# PlacaComNode.net
KiCad netlist of a schematic drawn in EAGLE
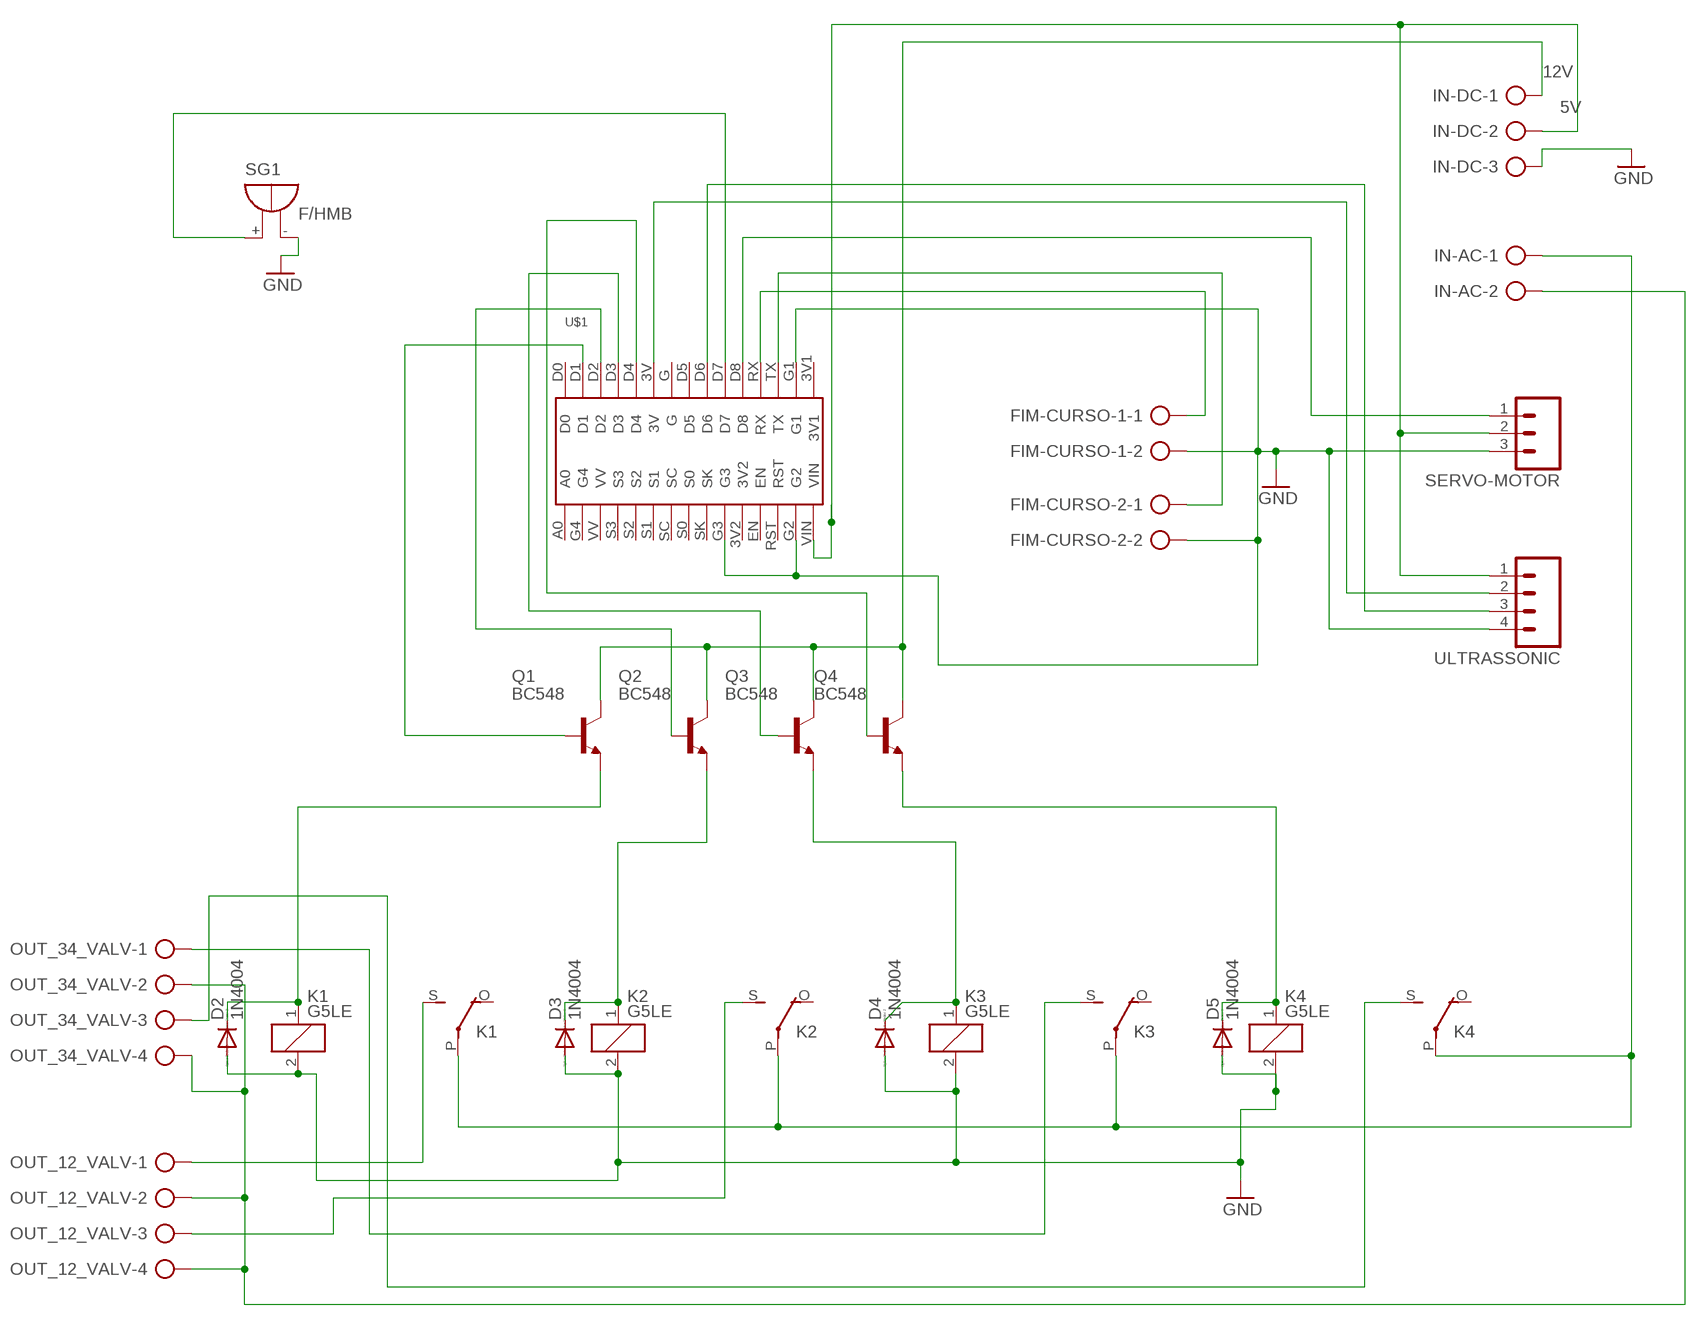
[diagram p0: schematic, sheet 1]

(export (version "E")
  (design (tool "Eeschema 10.0.6"))
  (components
    (comp (ref "D2")
      (value "1N4004")
      (footprint "eagle-import:DO41-10")
      (libsource (lib "eagle-import") (part "1N4004"))
    )
    (comp (ref "D3")
      (value "1N4004")
      (footprint "eagle-import:DO41-10")
      (libsource (lib "eagle-import") (part "1N4004"))
    )
    (comp (ref "D4")
      (value "1N4004")
      (footprint "eagle-import:DO41-10")
      (libsource (lib "eagle-import") (part "1N4004"))
    )
    (comp (ref "D5")
      (value "1N4004")
      (footprint "eagle-import:DO41-10")
      (libsource (lib "eagle-import") (part "1N4004"))
    )
    (comp (ref "FIM-CURSO-1")
      (value "AK500/2-H")
      (footprint "eagle-import:AK500_2-H")
      (libsource (lib "eagle-import") (part "AK500/2-H"))
    )
    (comp (ref "FIM-CURSO-2")
      (value "AK500/2-H")
      (footprint "eagle-import:AK500_2-H")
      (libsource (lib "eagle-import") (part "AK500/2-H"))
    )
    (comp (ref "IN-AC")
      (value "AK500/2-H")
      (footprint "eagle-import:AK500_2-H")
      (libsource (lib "eagle-import") (part "AK500/2-H"))
    )
    (comp (ref "IN-DC")
      (value "AK500/3-H")
      (footprint "eagle-import:AK500_3-H")
      (libsource (lib "eagle-import") (part "AK500/3-H"))
    )
    (comp (ref "K1")
      (value "G5LE")
      (footprint "eagle-import:G5LE")
      (libsource (lib "eagle-import") (part "G5LE"))
    )
    (comp (ref "K2")
      (value "G5LE")
      (footprint "eagle-import:G5LE")
      (libsource (lib "eagle-import") (part "G5LE"))
    )
    (comp (ref "K3")
      (value "G5LE")
      (footprint "eagle-import:G5LE")
      (libsource (lib "eagle-import") (part "G5LE"))
    )
    (comp (ref "K4")
      (value "G5LE")
      (footprint "eagle-import:G5LE")
      (libsource (lib "eagle-import") (part "G5LE"))
    )
    (comp (ref "OUT_12_VALV")
      (value "AK500/4-H")
      (footprint "eagle-import:AK500_4-H")
      (libsource (lib "eagle-import") (part "AK500/4-H"))
    )
    (comp (ref "OUT_34_VALV")
      (value "AK500/4-H")
      (footprint "eagle-import:AK500_4-H")
      (libsource (lib "eagle-import") (part "AK500/4-H"))
    )
    (comp (ref "Q1")
      (value "BC548")
      (footprint "eagle-import:TO92-EBC")
      (libsource (lib "eagle-import") (part "BC548"))
    )
    (comp (ref "Q2")
      (value "BC548")
      (footprint "eagle-import:TO92-EBC")
      (libsource (lib "eagle-import") (part "BC548"))
    )
    (comp (ref "Q3")
      (value "BC548")
      (footprint "eagle-import:TO92-EBC")
      (libsource (lib "eagle-import") (part "BC548"))
    )
    (comp (ref "Q4")
      (value "BC548")
      (footprint "eagle-import:TO92-EBC")
      (libsource (lib "eagle-import") (part "BC548"))
    )
    (comp (ref "SERVO-MOTOR")
      (value "M03")
      (footprint "eagle-import:03P")
      (libsource (lib "eagle-import") (part "M03"))
    )
    (comp (ref "SG1")
      (value "F/HMB")
      (footprint "eagle-import:F_HMB")
      (libsource (lib "eagle-import") (part "F/HMB"))
    )
    (comp (ref "U$1")
      (value "LOLIN")
      (footprint "eagle-import:LOLIN")
      (libsource (lib "eagle-import") (part "LOLIN"))
    )
    (comp (ref "ULTRASSONIC")
      (value "M04")
      (footprint "eagle-import:04P")
      (libsource (lib "eagle-import") (part "M04"))
    )
  )
  (nets
    (net (code "1") (name "/5V") (class "Default")
      (node (ref "IN-DC") (pin "2") (pinfunction "KL_2") (pintype "passive"))
      (node (ref "SERVO-MOTOR") (pin "2") (pinfunction "2_2") (pintype "passive"))
      (node (ref "U$1") (pin "VIN") (pinfunction "VIN_VIN") (pintype "bidirectional"))
      (node (ref "ULTRASSONIC") (pin "1") (pinfunction "1_1") (pintype "passive"))
    )
    (net (code "2") (name "/12V") (class "Default")
      (node (ref "IN-DC") (pin "1") (pinfunction "KL_1") (pintype "passive"))
      (node (ref "Q1") (pin "C") (pinfunction "C_C") (pintype "passive"))
      (node (ref "Q2") (pin "C") (pinfunction "C_C") (pintype "passive"))
      (node (ref "Q3") (pin "C") (pinfunction "C_C") (pintype "passive"))
      (node (ref "Q4") (pin "C") (pinfunction "C_C") (pintype "passive"))
    )
    (net (code "3") (name "GND") (class "Default")
      (node (ref "D2") (pin "A") (pinfunction "A_A") (pintype "passive"))
      (node (ref "D3") (pin "A") (pinfunction "A_A") (pintype "passive"))
      (node (ref "D4") (pin "A") (pinfunction "A_A") (pintype "passive"))
      (node (ref "D5") (pin "A") (pinfunction "A_A") (pintype "passive"))
      (node (ref "FIM-CURSO-1") (pin "2") (pinfunction "KL_2") (pintype "passive"))
      (node (ref "FIM-CURSO-2") (pin "2") (pinfunction "KL_2") (pintype "passive"))
      (node (ref "IN-DC") (pin "3") (pinfunction "KL_3") (pintype "passive"))
      (node (ref "K1") (pin "2") (pinfunction "2_2") (pintype "passive"))
      (node (ref "K2") (pin "2") (pinfunction "2_2") (pintype "passive"))
      (node (ref "K3") (pin "2") (pinfunction "2_2") (pintype "passive"))
      (node (ref "K4") (pin "2") (pinfunction "2_2") (pintype "passive"))
      (node (ref "SERVO-MOTOR") (pin "3") (pinfunction "3_3") (pintype "passive"))
      (node (ref "SG1") (pin "-") (pinfunction "-_-") (pintype "passive"))
      (node (ref "U$1") (pin "G1") (pinfunction "G1_G1") (pintype "bidirectional"))
      (node (ref "U$1") (pin "G2") (pinfunction "G2_G2") (pintype "bidirectional"))
      (node (ref "U$1") (pin "G3") (pinfunction "G3_G3") (pintype "bidirectional"))
      (node (ref "ULTRASSONIC") (pin "4") (pinfunction "4_4") (pintype "passive"))
    )
    (net (code "4") (name "Net-(D2-PadC)") (class "Default")
      (node (ref "D2") (pin "C") (pinfunction "C_C") (pintype "passive"))
      (node (ref "K1") (pin "1") (pinfunction "1_1") (pintype "passive"))
      (node (ref "Q1") (pin "E") (pinfunction "E_E") (pintype "passive"))
    )
    (net (code "5") (name "Net-(D3-PadC)") (class "Default")
      (node (ref "D3") (pin "C") (pinfunction "C_C") (pintype "passive"))
      (node (ref "K2") (pin "1") (pinfunction "1_1") (pintype "passive"))
      (node (ref "Q2") (pin "E") (pinfunction "E_E") (pintype "passive"))
    )
    (net (code "6") (name "Net-(D4-PadC)") (class "Default")
      (node (ref "D4") (pin "C") (pinfunction "C_C") (pintype "passive"))
      (node (ref "K3") (pin "1") (pinfunction "1_1") (pintype "passive"))
      (node (ref "Q3") (pin "E") (pinfunction "E_E") (pintype "passive"))
    )
    (net (code "7") (name "Net-(D5-PadC)") (class "Default")
      (node (ref "D5") (pin "C") (pinfunction "C_C") (pintype "passive"))
      (node (ref "K4") (pin "1") (pinfunction "1_1") (pintype "passive"))
      (node (ref "Q4") (pin "E") (pinfunction "E_E") (pintype "passive"))
    )
    (net (code "8") (name "Net-(FIM-CURSO-1A-KL)") (class "Default")
      (node (ref "FIM-CURSO-1") (pin "1") (pinfunction "KL_1") (pintype "passive"))
      (node (ref "U$1") (pin "RX") (pinfunction "RX_RX") (pintype "bidirectional"))
    )
    (net (code "9") (name "Net-(FIM-CURSO-2A-KL)") (class "Default")
      (node (ref "FIM-CURSO-2") (pin "1") (pinfunction "KL_1") (pintype "passive"))
      (node (ref "U$1") (pin "TX") (pinfunction "TX_TX") (pintype "bidirectional"))
    )
    (net (code "10") (name "Net-(IN-ACA-KL)") (class "Default")
      (node (ref "IN-AC") (pin "1") (pinfunction "KL_1") (pintype "passive"))
      (node (ref "K1") (pin "P") (pinfunction "P_P") (pintype "passive"))
      (node (ref "K2") (pin "P") (pinfunction "P_P") (pintype "passive"))
      (node (ref "K3") (pin "P") (pinfunction "P_P") (pintype "passive"))
      (node (ref "K4") (pin "P") (pinfunction "P_P") (pintype "passive"))
    )
    (net (code "11") (name "Net-(IN-ACB-KL)") (class "Default")
      (node (ref "IN-AC") (pin "2") (pinfunction "KL_2") (pintype "passive"))
      (node (ref "OUT_12_VALV") (pin "2") (pinfunction "KL_2") (pintype "passive"))
      (node (ref "OUT_12_VALV") (pin "4") (pinfunction "KL_4") (pintype "passive"))
      (node (ref "OUT_34_VALV") (pin "2") (pinfunction "KL_2") (pintype "passive"))
      (node (ref "OUT_34_VALV") (pin "4") (pinfunction "KL_4") (pintype "passive"))
    )
    (net (code "12") (name "Net-(OUT_12_VALVA-KL)") (class "Default")
      (node (ref "K1") (pin "S") (pinfunction "S_S") (pintype "passive"))
      (node (ref "OUT_12_VALV") (pin "1") (pinfunction "KL_1") (pintype "passive"))
    )
    (net (code "13") (name "Net-(OUT_12_VALVC-KL)") (class "Default")
      (node (ref "K2") (pin "S") (pinfunction "S_S") (pintype "passive"))
      (node (ref "OUT_12_VALV") (pin "3") (pinfunction "KL_3") (pintype "passive"))
    )
    (net (code "14") (name "Net-(OUT_34_VALVA-KL)") (class "Default")
      (node (ref "K3") (pin "S") (pinfunction "S_S") (pintype "passive"))
      (node (ref "OUT_34_VALV") (pin "1") (pinfunction "KL_1") (pintype "passive"))
    )
    (net (code "15") (name "Net-(OUT_34_VALVC-KL)") (class "Default")
      (node (ref "K4") (pin "S") (pinfunction "S_S") (pintype "passive"))
      (node (ref "OUT_34_VALV") (pin "3") (pinfunction "KL_3") (pintype "passive"))
    )
    (net (code "16") (name "Net-(Q1-PadB)") (class "Default")
      (node (ref "Q1") (pin "B") (pinfunction "B_B") (pintype "passive"))
      (node (ref "U$1") (pin "D1") (pinfunction "D1_D1") (pintype "bidirectional"))
    )
    (net (code "17") (name "Net-(Q2-PadB)") (class "Default")
      (node (ref "Q2") (pin "B") (pinfunction "B_B") (pintype "passive"))
      (node (ref "U$1") (pin "D2") (pinfunction "D2_D2") (pintype "bidirectional"))
    )
    (net (code "18") (name "Net-(Q3-PadB)") (class "Default")
      (node (ref "Q3") (pin "B") (pinfunction "B_B") (pintype "passive"))
      (node (ref "U$1") (pin "D3") (pinfunction "D3_D3") (pintype "bidirectional"))
    )
    (net (code "19") (name "Net-(Q4-PadB)") (class "Default")
      (node (ref "Q4") (pin "B") (pinfunction "B_B") (pintype "passive"))
      (node (ref "U$1") (pin "D4") (pinfunction "D4_D4") (pintype "bidirectional"))
    )
    (net (code "20") (name "Net-(SERVO-MOTOR-Pad1)") (class "Default")
      (node (ref "SERVO-MOTOR") (pin "1") (pinfunction "1_1") (pintype "passive"))
      (node (ref "U$1") (pin "D8") (pinfunction "D8_D8") (pintype "bidirectional"))
    )
    (net (code "21") (name "Net-(SG1-Pad+)") (class "Default")
      (node (ref "SG1") (pin "+") (pinfunction "+_+") (pintype "passive"))
      (node (ref "U$1") (pin "D7") (pinfunction "D7_D7") (pintype "bidirectional"))
    )
    (net (code "22") (name "Net-(U$1-Pad3V)") (class "Default")
      (node (ref "U$1") (pin "3V") (pinfunction "3V_3V") (pintype "bidirectional"))
      (node (ref "ULTRASSONIC") (pin "2") (pinfunction "2_2") (pintype "passive"))
    )
    (net (code "23") (name "Net-(U$1-PadD6)") (class "Default")
      (node (ref "U$1") (pin "D6") (pinfunction "D6_D6") (pintype "bidirectional"))
      (node (ref "ULTRASSONIC") (pin "3") (pinfunction "3_3") (pintype "passive"))
    )
    (net (code "24") (name "unconnected-(K1-PadO)") (class "Default")
      (node (ref "K1") (pin "O") (pinfunction "O_O") (pintype "passive"))
    )
    (net (code "25") (name "unconnected-(K2-PadO)") (class "Default")
      (node (ref "K2") (pin "O") (pinfunction "O_O") (pintype "passive"))
    )
    (net (code "26") (name "unconnected-(K3-PadO)") (class "Default")
      (node (ref "K3") (pin "O") (pinfunction "O_O") (pintype "passive"))
    )
    (net (code "27") (name "unconnected-(K4-PadO)") (class "Default")
      (node (ref "K4") (pin "O") (pinfunction "O_O") (pintype "passive"))
    )
    (net (code "28") (name "unconnected-(U$1-Pad3V1)") (class "Default")
      (node (ref "U$1") (pin "3V1") (pinfunction "3V1_3V1") (pintype "bidirectional"))
    )
    (net (code "29") (name "unconnected-(U$1-Pad3V2)") (class "Default")
      (node (ref "U$1") (pin "3V2") (pinfunction "3V2_3V2") (pintype "bidirectional"))
    )
    (net (code "30") (name "unconnected-(U$1-PadA0)") (class "Default")
      (node (ref "U$1") (pin "A0") (pinfunction "A0_A0") (pintype "bidirectional"))
    )
    (net (code "31") (name "unconnected-(U$1-PadD0)") (class "Default")
      (node (ref "U$1") (pin "D0") (pinfunction "D0_D0") (pintype "bidirectional"))
    )
    (net (code "32") (name "unconnected-(U$1-PadD5)") (class "Default")
      (node (ref "U$1") (pin "D5") (pinfunction "D5_D5") (pintype "bidirectional"))
    )
    (net (code "33") (name "unconnected-(U$1-PadEN)") (class "Default")
      (node (ref "U$1") (pin "EN") (pinfunction "EN_EN") (pintype "bidirectional"))
    )
    (net (code "34") (name "unconnected-(U$1-PadG)") (class "Default")
      (node (ref "U$1") (pin "G") (pinfunction "G_G") (pintype "bidirectional"))
    )
    (net (code "35") (name "unconnected-(U$1-PadG4)") (class "Default")
      (node (ref "U$1") (pin "G4") (pinfunction "G4_G4") (pintype "bidirectional"))
    )
    (net (code "36") (name "unconnected-(U$1-PadRST)") (class "Default")
      (node (ref "U$1") (pin "RST") (pinfunction "RST_RST") (pintype "bidirectional"))
    )
    (net (code "37") (name "unconnected-(U$1-PadS0)") (class "Default")
      (node (ref "U$1") (pin "S0") (pinfunction "S0_S0") (pintype "bidirectional"))
    )
    (net (code "38") (name "unconnected-(U$1-PadS1)") (class "Default")
      (node (ref "U$1") (pin "S1") (pinfunction "S1_S1") (pintype "bidirectional"))
    )
    (net (code "39") (name "unconnected-(U$1-PadS2)") (class "Default")
      (node (ref "U$1") (pin "S2") (pinfunction "S2_S2") (pintype "bidirectional"))
    )
    (net (code "40") (name "unconnected-(U$1-PadS3)") (class "Default")
      (node (ref "U$1") (pin "S3") (pinfunction "S3_S3") (pintype "bidirectional"))
    )
    (net (code "41") (name "unconnected-(U$1-PadSC)") (class "Default")
      (node (ref "U$1") (pin "SC") (pinfunction "SC_SC") (pintype "bidirectional"))
    )
    (net (code "42") (name "unconnected-(U$1-PadSK)") (class "Default")
      (node (ref "U$1") (pin "SK") (pinfunction "SK_SK") (pintype "bidirectional"))
    )
    (net (code "43") (name "unconnected-(U$1-PadVV)") (class "Default")
      (node (ref "U$1") (pin "VV") (pinfunction "VV_VV") (pintype "bidirectional"))
    )
  )
)
